# Power.net
KiCad netlist of a schematic drawn in Altium Designer
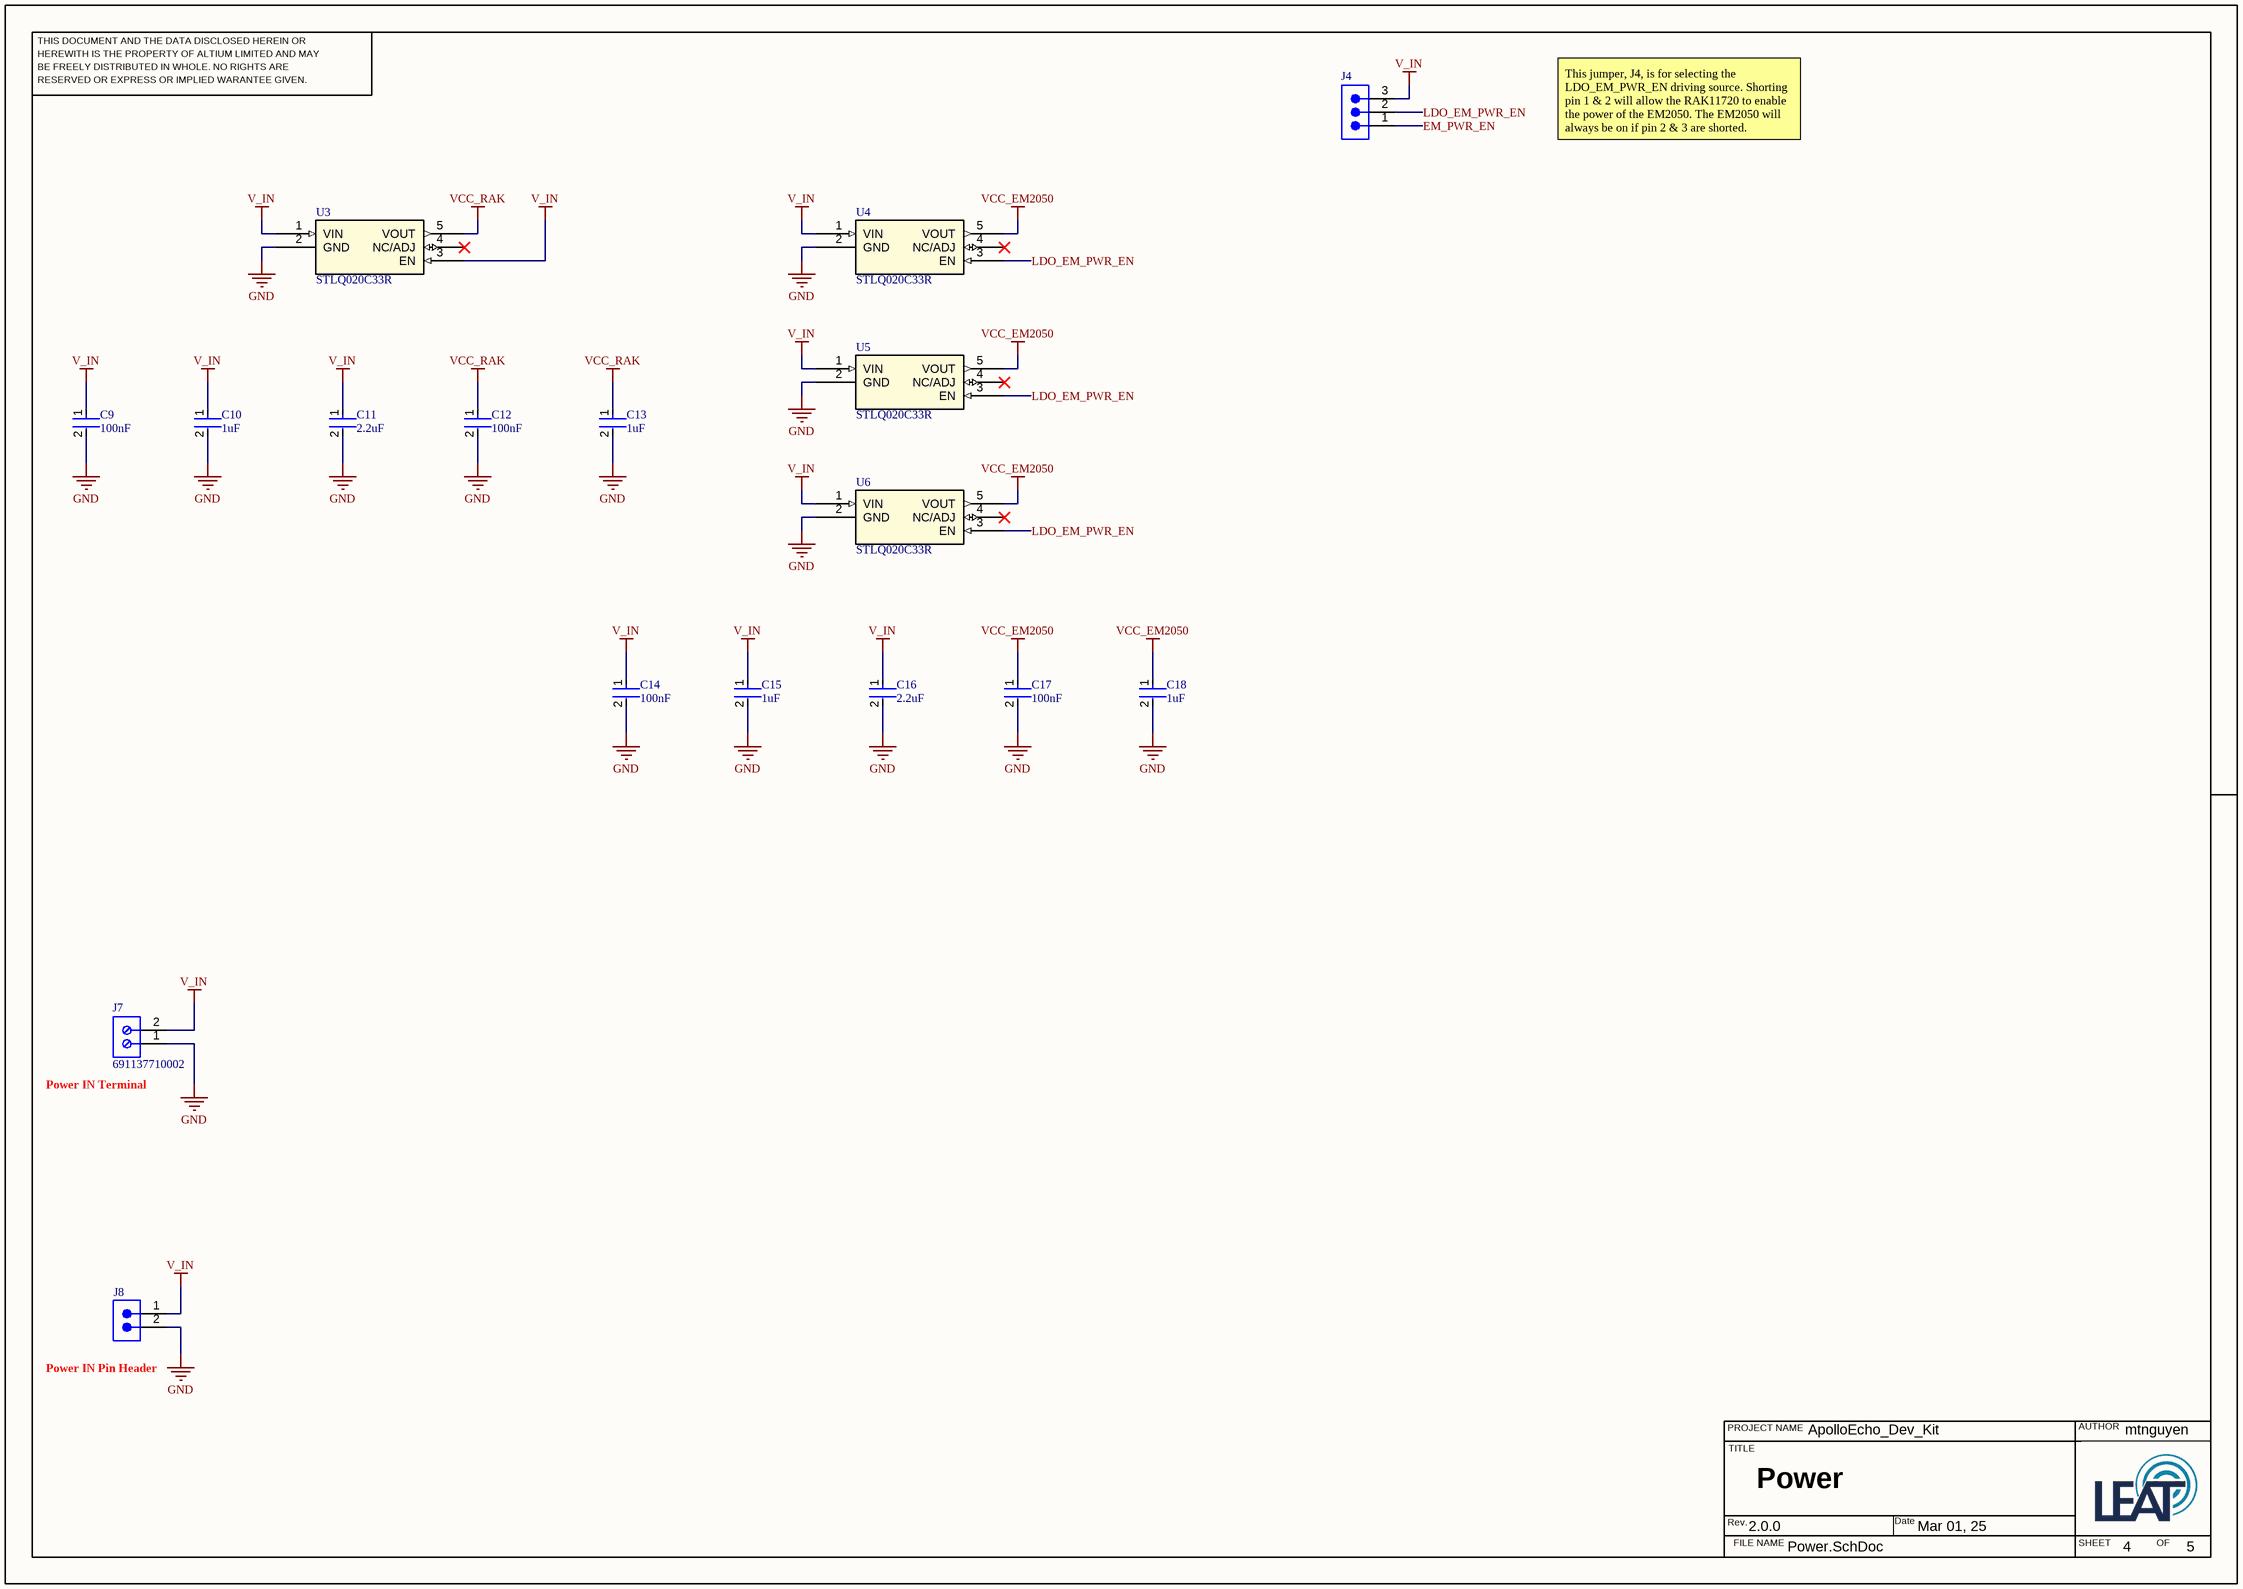
[diagram p0: Power.SchDoc]

(export (version "E")
  (design (tool "Eeschema 10.0.6"))
  (components
    (comp (ref "C9")
      (value "0402ZD104KAT2A")
      (footprint "FP-0402-L_1_0_1-W_0_5_0_1-IPC_C")
      (description "General Purpose Ceramic Capacitor, 0402, 100nF, 10%, X5R, 15%, 10V")
      (fields
        (field (name "VOLTAGE") "10V")
        (field (name "TOLERANCE") "10%")
        (field (name "CAPACITANCE") "100nF")
      )
      (libsource (lib "Altium Content Vault") (part "b4654b650e69147ec39a6b967a45e02"))
    )
    (comp (ref "C10")
      (value "EMK105BJ105KV-F")
      (footprint "FP-0402-L_1_0_0_05-W_0_5-IPC_A")
      (description "None")
      (fields (field (name "TOLERANCE") "10%") (field (name "CAPACITANCE") "1uF"))
      (libsource (lib "Altium Content Vault") (part "b4654b650e69147ec39a6b967a45e02"))
    )
    (comp (ref "C11")
      (value "C1005X5R1A225K050BC")
      (footprint "FP-C1005-050-0_05-IPC_A")
      (description "Multilayer Ceramic Capacitors 2.2μF ±10% 10V X5R SMD 0402")
      (fields
        (field (name "TOLERANCE") "10%")
        (field (name "VOLTAGE") "10V")
        (field (name "CAPACITANCE") "2.2uF")
      )
      (libsource (lib "Altium Content Vault") (part "b4654b650e69147ec39a6b967a45e02"))
    )
    (comp (ref "C12")
      (value "0402ZD104KAT2A")
      (footprint "FP-0402-L_1_0_1-W_0_5_0_1-IPC_C")
      (description "General Purpose Ceramic Capacitor, 0402, 100nF, 10%, X5R, 15%, 10V")
      (fields
        (field (name "VOLTAGE") "10V")
        (field (name "TOLERANCE") "10%")
        (field (name "CAPACITANCE") "100nF")
      )
      (libsource (lib "Altium Content Vault") (part "b4654b650e69147ec39a6b967a45e02"))
    )
    (comp (ref "C13")
      (value "EMK105BJ105KV-F")
      (footprint "FP-0402-L_1_0_0_05-W_0_5-IPC_A")
      (description "None")
      (fields (field (name "TOLERANCE") "10%") (field (name "CAPACITANCE") "1uF"))
      (libsource (lib "Altium Content Vault") (part "b4654b650e69147ec39a6b967a45e02"))
    )
    (comp (ref "C14")
      (value "0402ZD104KAT2A")
      (footprint "FP-0402-L_1_0_1-W_0_5_0_1-IPC_C")
      (description "General Purpose Ceramic Capacitor, 0402, 100nF, 10%, X5R, 15%, 10V")
      (fields
        (field (name "VOLTAGE") "10V")
        (field (name "TOLERANCE") "10%")
        (field (name "CAPACITANCE") "100nF")
      )
      (libsource (lib "Altium Content Vault") (part "b4654b650e69147ec39a6b967a45e02"))
    )
    (comp (ref "C15")
      (value "EMK105BJ105KV-F")
      (footprint "FP-0402-L_1_0_0_05-W_0_5-IPC_A")
      (description "None")
      (fields (field (name "TOLERANCE") "10%") (field (name "CAPACITANCE") "1uF"))
      (libsource (lib "Altium Content Vault") (part "b4654b650e69147ec39a6b967a45e02"))
    )
    (comp (ref "C16")
      (value "C1005X5R1A225K050BC")
      (footprint "FP-C1005-050-0_05-IPC_A")
      (description "Multilayer Ceramic Capacitors 2.2μF ±10% 10V X5R SMD 0402")
      (fields
        (field (name "TOLERANCE") "10%")
        (field (name "VOLTAGE") "10V")
        (field (name "CAPACITANCE") "2.2uF")
      )
      (libsource (lib "Altium Content Vault") (part "b4654b650e69147ec39a6b967a45e02"))
    )
    (comp (ref "C17")
      (value "0402ZD104KAT2A")
      (footprint "FP-0402-L_1_0_1-W_0_5_0_1-IPC_C")
      (description "General Purpose Ceramic Capacitor, 0402, 100nF, 10%, X5R, 15%, 10V")
      (fields
        (field (name "VOLTAGE") "10V")
        (field (name "TOLERANCE") "10%")
        (field (name "CAPACITANCE") "100nF")
      )
      (libsource (lib "Altium Content Vault") (part "b4654b650e69147ec39a6b967a45e02"))
    )
    (comp (ref "C18")
      (value "EMK105BJ105KV-F")
      (footprint "FP-0402-L_1_0_0_05-W_0_5-IPC_A")
      (description "None")
      (fields (field (name "TOLERANCE") "10%") (field (name "CAPACITANCE") "1uF"))
      (libsource (lib "Altium Content Vault") (part "b4654b650e69147ec39a6b967a45e02"))
    )
    (comp (ref "J4")
      (value "61300311121")
      (footprint "61300311121")
      (libsource (lib "Altium Content Vault") (part "Header_Male_1R_03P"))
    )
    (comp (ref "J7")
      (value "691137710002")
      (footprint "691137710002")
      (libsource (lib "Altium Content Vault") (part "TBL - 1R - 02P - Screw"))
    )
    (comp (ref "J8")
      (value "61300211121")
      (footprint "61300211121")
      (libsource (lib "Altium Content Vault") (part "Header_Male_1R_02P"))
    )
    (comp (ref "U3")
      (value "STLQ020C33R")
      (footprint "SOT323-5L_STM")
      (description "No Description Available")
      (fields (field (name "COPYRIGHT") "Copyright (C) 2023 Ultra Librarian. All rights reserved."))
      (libsource (lib "EchoStar") (part "STLQ020C33R"))
    )
    (comp (ref "U4")
      (value "STLQ020C33R")
      (footprint "SOT323-5L_STM")
      (description "No Description Available")
      (fields (field (name "COPYRIGHT") "Copyright (C) 2023 Ultra Librarian. All rights reserved."))
      (libsource (lib "EchoStar") (part "STLQ020C33R"))
    )
    (comp (ref "U5")
      (value "STLQ020C33R")
      (footprint "SOT323-5L_STM")
      (description "No Description Available")
      (fields (field (name "COPYRIGHT") "Copyright (C) 2023 Ultra Librarian. All rights reserved."))
      (libsource (lib "EchoStar") (part "STLQ020C33R"))
    )
    (comp (ref "U6")
      (value "STLQ020C33R")
      (footprint "SOT323-5L_STM")
      (description "No Description Available")
      (fields (field (name "COPYRIGHT") "Copyright (C) 2023 Ultra Librarian. All rights reserved."))
      (libsource (lib "EchoStar") (part "STLQ020C33R"))
    )
  )
  (nets
    (net (code "1") (name "/EM_PWR_EN") (class "Default")
      (node (ref "J4") (pin "1") (pinfunction "1_1") (pintype "passive"))
    )
    (net (code "2") (name "/LDO_EM_PWR_EN") (class "Default")
      (node (ref "J4") (pin "2") (pinfunction "2_2") (pintype "passive"))
      (node (ref "U4") (pin "3") (pinfunction "EN_3") (pintype "input"))
      (node (ref "U5") (pin "3") (pinfunction "EN_3") (pintype "input"))
      (node (ref "U6") (pin "3") (pinfunction "EN_3") (pintype "input"))
    )
    (net (code "3") (name "GND") (class "Default")
      (node (ref "C10") (pin "2") (pinfunction "2_2") (pintype "passive"))
      (node (ref "C11") (pin "2") (pinfunction "2_2") (pintype "passive"))
      (node (ref "C12") (pin "2") (pinfunction "2_2") (pintype "passive"))
      (node (ref "C13") (pin "2") (pinfunction "2_2") (pintype "passive"))
      (node (ref "C14") (pin "2") (pinfunction "2_2") (pintype "passive"))
      (node (ref "C15") (pin "2") (pinfunction "2_2") (pintype "passive"))
      (node (ref "C16") (pin "2") (pinfunction "2_2") (pintype "passive"))
      (node (ref "C17") (pin "2") (pinfunction "2_2") (pintype "passive"))
      (node (ref "C18") (pin "2") (pinfunction "2_2") (pintype "passive"))
      (node (ref "C9") (pin "2") (pinfunction "2_2") (pintype "passive"))
      (node (ref "J7") (pin "1") (pinfunction "1_1") (pintype "passive"))
      (node (ref "J8") (pin "2") (pinfunction "2_2") (pintype "passive"))
      (node (ref "U3") (pin "2") (pinfunction "GND_2") (pintype "power_in"))
      (node (ref "U4") (pin "2") (pinfunction "GND_2") (pintype "power_in"))
      (node (ref "U5") (pin "2") (pinfunction "GND_2") (pintype "power_in"))
      (node (ref "U6") (pin "2") (pinfunction "GND_2") (pintype "power_in"))
    )
    (net (code "4") (name "VCC_EM2050") (class "Default")
      (node (ref "C17") (pin "1") (pinfunction "1_1") (pintype "passive"))
      (node (ref "C18") (pin "1") (pinfunction "1_1") (pintype "passive"))
      (node (ref "U4") (pin "5") (pinfunction "VOUT_5") (pintype "output"))
      (node (ref "U5") (pin "5") (pinfunction "VOUT_5") (pintype "output"))
      (node (ref "U6") (pin "5") (pinfunction "VOUT_5") (pintype "output"))
    )
    (net (code "5") (name "VCC_RAK") (class "Default")
      (node (ref "C12") (pin "1") (pinfunction "1_1") (pintype "passive"))
      (node (ref "C13") (pin "1") (pinfunction "1_1") (pintype "passive"))
      (node (ref "U3") (pin "5") (pinfunction "VOUT_5") (pintype "output"))
    )
    (net (code "6") (name "V_IN") (class "Default")
      (node (ref "C10") (pin "1") (pinfunction "1_1") (pintype "passive"))
      (node (ref "C11") (pin "1") (pinfunction "1_1") (pintype "passive"))
      (node (ref "C14") (pin "1") (pinfunction "1_1") (pintype "passive"))
      (node (ref "C15") (pin "1") (pinfunction "1_1") (pintype "passive"))
      (node (ref "C16") (pin "1") (pinfunction "1_1") (pintype "passive"))
      (node (ref "C9") (pin "1") (pinfunction "1_1") (pintype "passive"))
      (node (ref "J4") (pin "3") (pinfunction "3_3") (pintype "passive"))
      (node (ref "J7") (pin "2") (pinfunction "2_2") (pintype "passive"))
      (node (ref "J8") (pin "1") (pinfunction "1_1") (pintype "passive"))
      (node (ref "U3") (pin "1") (pinfunction "VIN_1") (pintype "input"))
      (node (ref "U3") (pin "3") (pinfunction "EN_3") (pintype "input"))
      (node (ref "U4") (pin "1") (pinfunction "VIN_1") (pintype "input"))
      (node (ref "U5") (pin "1") (pinfunction "VIN_1") (pintype "input"))
      (node (ref "U6") (pin "1") (pinfunction "VIN_1") (pintype "input"))
    )
    (net (code "7") (name "unconnected-(U3-NC{slash}ADJ-Pad4)") (class "Default")
      (node (ref "U3") (pin "4") (pinfunction "NC/ADJ_4") (pintype "bidirectional+no_connect"))
    )
    (net (code "8") (name "unconnected-(U4-NC{slash}ADJ-Pad4)") (class "Default")
      (node (ref "U4") (pin "4") (pinfunction "NC/ADJ_4") (pintype "bidirectional+no_connect"))
    )
    (net (code "9") (name "unconnected-(U5-NC{slash}ADJ-Pad4)") (class "Default")
      (node (ref "U5") (pin "4") (pinfunction "NC/ADJ_4") (pintype "bidirectional+no_connect"))
    )
    (net (code "10") (name "unconnected-(U6-NC{slash}ADJ-Pad4)") (class "Default")
      (node (ref "U6") (pin "4") (pinfunction "NC/ADJ_4") (pintype "bidirectional+no_connect"))
    )
  )
)
